# latch_sdc_sch.net
KiCad netlist of a schematic drawn in Altium Designer
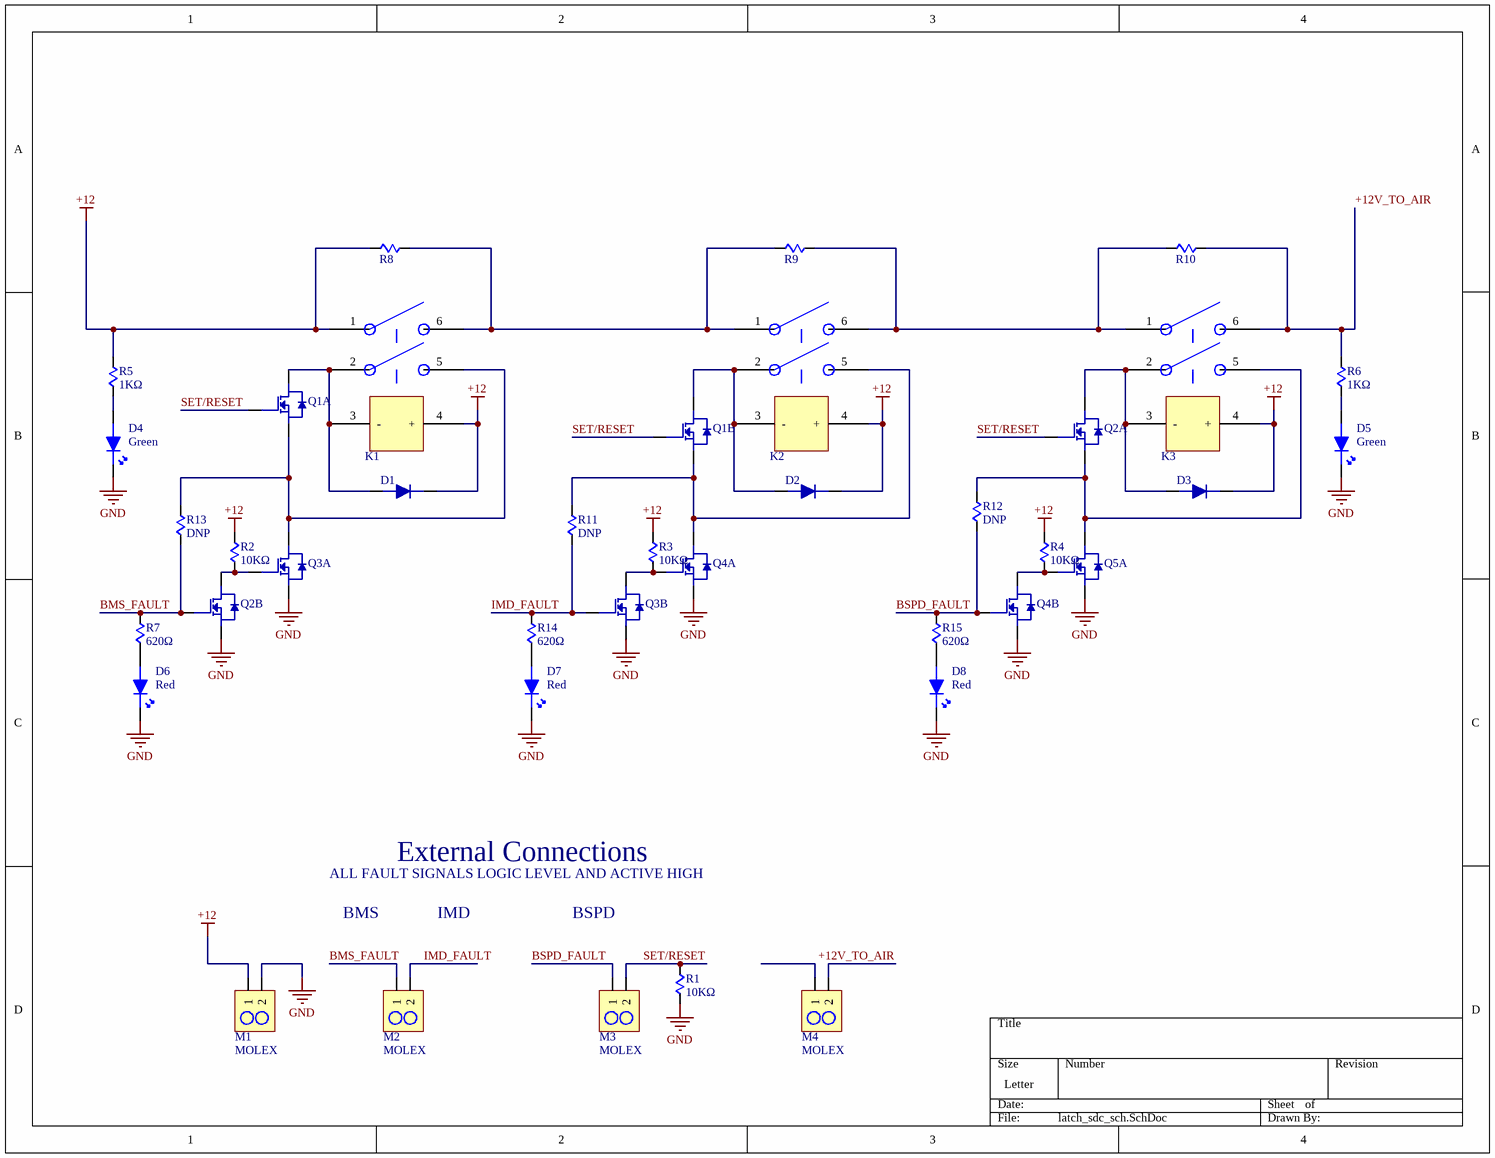
[diagram p0: latch_sdc_sch.SchDoc]

(export (version "E")
  (design (tool "Eeschema 10.0.6"))
  (components
    (comp (ref "D1")
      (value "SD560BTR")
      (footprint "DIOM4436X26N")
      (description "DIODE GEN PURP 600V 5A SMB")
      (fields (field (name "MANUFACTURER") "SMC"))
      (libsource (lib "latch_sdc_schlib") (part "SD560BTR"))
    )
    (comp (ref "D2")
      (value "SD560BTR")
      (footprint "DIOM4436X26N")
      (description "DIODE GEN PURP 600V 5A SMB")
      (fields (field (name "MANUFACTURER") "SMC"))
      (libsource (lib "latch_sdc_schlib") (part "SD560BTR"))
    )
    (comp (ref "D3")
      (value "SD560BTR")
      (footprint "DIOM4436X26N")
      (description "DIODE GEN PURP 600V 5A SMB")
      (fields (field (name "MANUFACTURER") "SMC"))
      (libsource (lib "latch_sdc_schlib") (part "SD560BTR"))
    )
    (comp (ref "D4")
      (value "Green")
      (footprint "LED GREEN")
      (description "WURTH ELEKTRONIK - 150060VS75000 - LED, 0603, B GREEN,  40MCD, 570NM")
      (libsource (lib "latch_sdc_schlib") (part "150060VS75000"))
    )
    (comp (ref "D5")
      (value "Green")
      (footprint "LED GREEN")
      (description "WURTH ELEKTRONIK - 150060VS75000 - LED, 0603, B GREEN,  40MCD, 570NM")
      (libsource (lib "latch_sdc_schlib") (part "150060VS75000"))
    )
    (comp (ref "D6")
      (value "Red")
      (footprint "LED RED")
      (description "WURTH ELEKTRONIK - 150060RS75000 - LED, 0603, RED, 250MCD, 625NM")
      (libsource (lib "latch_sdc_schlib") (part "150060RS75000"))
    )
    (comp (ref "D7")
      (value "Red")
      (footprint "LED RED")
      (description "WURTH ELEKTRONIK - 150060RS75000 - LED, 0603, RED, 250MCD, 625NM")
      (libsource (lib "latch_sdc_schlib") (part "150060RS75000"))
    )
    (comp (ref "D8")
      (value "Red")
      (footprint "LED RED")
      (description "WURTH ELEKTRONIK - 150060RS75000 - LED, 0603, RED, 250MCD, 625NM")
      (libsource (lib "latch_sdc_schlib") (part "150060RS75000"))
    )
    (comp (ref "K1")
      (value "3A")
      (footprint "RELAY02_FOOTPRINT")
      (fields
        (field (name "MANUFACTURER") "TE Connectivity")
        (field (name "MANUFACTURER PART NUMBER") "OSA-SS-212DM3,000")
      )
      (libsource (lib "latch_sdc_schlib") (part "OSA-SS-212DM3,000"))
    )
    (comp (ref "K2")
      (value "3A")
      (footprint "RELAY02_FOOTPRINT")
      (fields
        (field (name "MANUFACTURER") "TE Connectivity")
        (field (name "MANUFACTURER PART NUMBER") "OSA-SS-212DM3,000")
      )
      (libsource (lib "latch_sdc_schlib") (part "OSA-SS-212DM3,000"))
    )
    (comp (ref "K3")
      (value "3A")
      (footprint "RELAY02_FOOTPRINT")
      (fields
        (field (name "MANUFACTURER") "TE Connectivity")
        (field (name "MANUFACTURER PART NUMBER") "OSA-SS-212DM3,000")
      )
      (libsource (lib "latch_sdc_schlib") (part "OSA-SS-212DM3,000"))
    )
    (comp (ref "M1")
      (value "MOLEX")
      (footprint "MOLEX 1")
      (description "MOLEX - 43650-0200 - CONNECTOR, HEADER, 2POS, 1ROW, 3MM")
      (fields (field (name "MANUFACTURER") "Molex") (field (name "MANUFACTURER PART NUMBER") "43650-0200"))
      (libsource (lib "latch_sdc_schlib") (part "43650-0200"))
    )
    (comp (ref "M2")
      (value "MOLEX")
      (footprint "MOLEX 1")
      (description "MOLEX - 43650-0200 - CONNECTOR, HEADER, 2POS, 1ROW, 3MM")
      (fields (field (name "MANUFACTURER") "Molex") (field (name "MANUFACTURER PART NUMBER") "43650-0200"))
      (libsource (lib "latch_sdc_schlib") (part "43650-0200"))
    )
    (comp (ref "M3")
      (value "MOLEX")
      (footprint "MOLEX 1")
      (description "MOLEX - 43650-0200 - CONNECTOR, HEADER, 2POS, 1ROW, 3MM")
      (fields (field (name "MANUFACTURER") "Molex") (field (name "MANUFACTURER PART NUMBER") "43650-0200"))
      (libsource (lib "latch_sdc_schlib") (part "43650-0200"))
    )
    (comp (ref "M4")
      (value "MOLEX")
      (footprint "MOLEX 1")
      (description "MOLEX - 43650-0200 - CONNECTOR, HEADER, 2POS, 1ROW, 3MM")
      (fields (field (name "MANUFACTURER") "Molex") (field (name "MANUFACTURER PART NUMBER") "43650-0200"))
      (libsource (lib "latch_sdc_schlib") (part "43650-0200"))
    )
    (comp (ref "Q1")
      (value "DMN2029USD-13")
      (footprint "SOIC127P600X175-8N")
      (description "MOSFET 2N-CH 20V 5.8A 8SO")
      (fields (field (name "MANUFACTURER") "Diodes"))
      (libsource (lib "latch_sdc_schlib") (part "DMN2029USD-13"))
    )
    (comp (ref "Q2")
      (value "DMN2029USD-13")
      (footprint "SOIC127P600X175-8N")
      (description "MOSFET 2N-CH 20V 5.8A 8SO")
      (fields (field (name "MANUFACTURER") "Diodes"))
      (libsource (lib "latch_sdc_schlib") (part "DMN2029USD-13"))
    )
    (comp (ref "Q3")
      (value "DMN2029USD-13")
      (footprint "SOIC127P600X175-8N")
      (description "MOSFET 2N-CH 20V 5.8A 8SO")
      (fields (field (name "MANUFACTURER") "Diodes"))
      (libsource (lib "latch_sdc_schlib") (part "DMN2029USD-13"))
    )
    (comp (ref "Q4")
      (value "DMN2029USD-13")
      (footprint "SOIC127P600X175-8N")
      (description "MOSFET 2N-CH 20V 5.8A 8SO")
      (fields (field (name "MANUFACTURER") "Diodes"))
      (libsource (lib "latch_sdc_schlib") (part "DMN2029USD-13"))
    )
    (comp (ref "Q5")
      (value "DMN2029USD-13")
      (footprint "SOIC127P600X175-8N")
      (description "MOSFET 2N-CH 20V 5.8A 8SO")
      (fields (field (name "MANUFACTURER") "Diodes"))
      (libsource (lib "latch_sdc_schlib") (part "DMN2029USD-13"))
    )
    (comp (ref "R1")
      (value "10KΩ")
      (footprint "10KOHM")
      (description "RES 10K OHM 1% 1/8W 0603")
      (fields
        (field (name "MANUFACTURER") "Stackpole Electronics")
        (field (name "MANUFACTURER PART NUMBER") "RNCP0603FTD10K0")
      )
      (libsource (lib "latch_sdc_schlib") (part "RNCP0603FTD10K0"))
    )
    (comp (ref "R2")
      (value "10KΩ")
      (footprint "10KOHM")
      (description "RES 10K OHM 1% 1/8W 0603")
      (fields
        (field (name "MANUFACTURER") "Stackpole Electronics")
        (field (name "MANUFACTURER PART NUMBER") "RNCP0603FTD10K0")
      )
      (libsource (lib "latch_sdc_schlib") (part "RNCP0603FTD10K0"))
    )
    (comp (ref "R3")
      (value "10KΩ")
      (footprint "10KOHM")
      (description "RES 10K OHM 1% 1/8W 0603")
      (fields
        (field (name "MANUFACTURER") "Stackpole Electronics")
        (field (name "MANUFACTURER PART NUMBER") "RNCP0603FTD10K0")
      )
      (libsource (lib "latch_sdc_schlib") (part "RNCP0603FTD10K0"))
    )
    (comp (ref "R4")
      (value "10KΩ")
      (footprint "10KOHM")
      (description "RES 10K OHM 1% 1/8W 0603")
      (fields
        (field (name "MANUFACTURER") "Stackpole Electronics")
        (field (name "MANUFACTURER PART NUMBER") "RNCP0603FTD10K0")
      )
      (libsource (lib "latch_sdc_schlib") (part "RNCP0603FTD10K0"))
    )
    (comp (ref "R5")
      (value "1KΩ")
      (footprint "1KOHM")
      (description "YAGEO - RC0201FR-071KL - DICKSCHICHTWIDERSTAND 1K 1% 0.05W 0201")
      (fields (field (name "TOLERANCE") "1%"))
      (libsource (lib "latch_sdc_schlib") (part "RC0201FR-071KL"))
    )
    (comp (ref "R6")
      (value "1KΩ")
      (footprint "1KOHM")
      (description "YAGEO - RC0201FR-071KL - DICKSCHICHTWIDERSTAND 1K 1% 0.05W 0201")
      (fields (field (name "TOLERANCE") "1%"))
      (libsource (lib "latch_sdc_schlib") (part "RC0201FR-071KL"))
    )
    (comp (ref "R7")
      (value "620Ω")
      (footprint "620OHM")
      (description "RC0201 Series 0201 0.05 W 620 Ohms 1% ±200 ppm/°C SMT Thick Film Chip Resistor")
      (fields (field (name "TOLERANCE") "1%"))
      (libsource (lib "latch_sdc_schlib") (part "RC0201FR-07620RL"))
    )
    (comp (ref "R8")
      (value "RMCF0603ZT0R00")
      (footprint "0OHM")
      (description "RES 0 OHM JUMPER 1/10W 0603")
      (fields (field (name "MANUFACTURER") "Stackpole Electronics"))
      (libsource (lib "latch_sdc_schlib") (part "RMCF0603ZT0R00"))
    )
    (comp (ref "R9")
      (value "RMCF0603ZT0R00")
      (footprint "0OHM")
      (description "RES 0 OHM JUMPER 1/10W 0603")
      (fields (field (name "MANUFACTURER") "Stackpole Electronics"))
      (libsource (lib "latch_sdc_schlib") (part "RMCF0603ZT0R00"))
    )
    (comp (ref "R10")
      (value "RMCF0603ZT0R00")
      (footprint "0OHM")
      (description "RES 0 OHM JUMPER 1/10W 0603")
      (fields (field (name "MANUFACTURER") "Stackpole Electronics"))
      (libsource (lib "latch_sdc_schlib") (part "RMCF0603ZT0R00"))
    )
    (comp (ref "R11")
      (value "DNP")
      (footprint "0OHM")
      (description "RES 0 OHM JUMPER 1/10W 0603")
      (fields
        (field (name "MANUFACTURER") "Stackpole Electronics")
        (field (name "MANUFACTURER PART NUMBER") "RMCF0603ZT0R00")
      )
      (libsource (lib "latch_sdc_schlib") (part "RMCF0603ZT0R00_1"))
    )
    (comp (ref "R12")
      (value "DNP")
      (footprint "0OHM")
      (description "RES 0 OHM JUMPER 1/10W 0603")
      (fields
        (field (name "MANUFACTURER") "Stackpole Electronics")
        (field (name "MANUFACTURER PART NUMBER") "RMCF0603ZT0R00")
      )
      (libsource (lib "latch_sdc_schlib") (part "RMCF0603ZT0R00_1"))
    )
    (comp (ref "R13")
      (value "DNP")
      (footprint "0OHM")
      (description "RES 0 OHM JUMPER 1/10W 0603")
      (fields
        (field (name "MANUFACTURER") "Stackpole Electronics")
        (field (name "MANUFACTURER PART NUMBER") "RMCF0603ZT0R00")
      )
      (libsource (lib "latch_sdc_schlib") (part "RMCF0603ZT0R00_1"))
    )
    (comp (ref "R14")
      (value "620Ω")
      (footprint "620OHM")
      (description "RC0201 Series 0201 0.05 W 620 Ohms 1% ±200 ppm/°C SMT Thick Film Chip Resistor")
      (fields (field (name "TOLERANCE") "1%"))
      (libsource (lib "latch_sdc_schlib") (part "RC0201FR-07620RL"))
    )
    (comp (ref "R15")
      (value "620Ω")
      (footprint "620OHM")
      (description "RC0201 Series 0201 0.05 W 620 Ohms 1% ±200 ppm/°C SMT Thick Film Chip Resistor")
      (fields (field (name "TOLERANCE") "1%"))
      (libsource (lib "latch_sdc_schlib") (part "RC0201FR-07620RL"))
    )
  )
  (nets
    (net (code "1") (name "+12") (class "Default")
      (node (ref "D1") (pin "2") (pinfunction "2_2") (pintype "passive"))
      (node (ref "D2") (pin "2") (pinfunction "2_2") (pintype "passive"))
      (node (ref "D3") (pin "2") (pinfunction "2_2") (pintype "passive"))
      (node (ref "K1") (pin "1") (pintype "passive"))
      (node (ref "K1") (pin "4") (pinfunction "+_4") (pintype "passive"))
      (node (ref "K2") (pin "4") (pinfunction "+_4") (pintype "passive"))
      (node (ref "K3") (pin "4") (pinfunction "+_4") (pintype "passive"))
      (node (ref "M1") (pin "1") (pinfunction "1_1") (pintype "passive"))
      (node (ref "R2") (pin "1") (pinfunction "1_1") (pintype "passive"))
      (node (ref "R3") (pin "1") (pinfunction "1_1") (pintype "passive"))
      (node (ref "R4") (pin "1") (pinfunction "1_1") (pintype "passive"))
      (node (ref "R5") (pin "2") (pinfunction "2_2") (pintype "passive"))
      (node (ref "R8") (pin "1") (pinfunction "1_1") (pintype "passive"))
    )
    (net (code "2") (name "/+12V_TO_AIR") (class "Default")
      (node (ref "K3") (pin "6") (pintype "passive"))
      (node (ref "M4") (pin "2") (pinfunction "2_2") (pintype "passive"))
      (node (ref "R10") (pin "2") (pinfunction "2_2") (pintype "passive"))
      (node (ref "R6") (pin "2") (pinfunction "2_2") (pintype "passive"))
    )
    (net (code "3") (name "/BMS_FAULT") (class "Default")
      (node (ref "M2") (pin "1") (pinfunction "1_1") (pintype "passive"))
      (node (ref "Q2") (pin "4") (pinfunction "G2_4") (pintype "passive"))
      (node (ref "R13") (pin "1") (pinfunction "1_1") (pintype "passive"))
      (node (ref "R7") (pin "2") (pinfunction "2_2") (pintype "passive"))
    )
    (net (code "4") (name "/BSPD_FAULT") (class "Default")
      (node (ref "M3") (pin "1") (pinfunction "1_1") (pintype "passive"))
      (node (ref "Q4") (pin "4") (pinfunction "G2_4") (pintype "passive"))
      (node (ref "R12") (pin "1") (pinfunction "1_1") (pintype "passive"))
      (node (ref "R15") (pin "2") (pinfunction "2_2") (pintype "passive"))
    )
    (net (code "5") (name "/IMD_FAULT") (class "Default")
      (node (ref "M2") (pin "2") (pinfunction "2_2") (pintype "passive"))
      (node (ref "Q3") (pin "4") (pinfunction "G2_4") (pintype "passive"))
      (node (ref "R11") (pin "1") (pinfunction "1_1") (pintype "passive"))
      (node (ref "R14") (pin "2") (pinfunction "2_2") (pintype "passive"))
    )
    (net (code "6") (name "/SET{slash}RESET") (class "Default")
      (node (ref "M3") (pin "2") (pinfunction "2_2") (pintype "passive"))
      (node (ref "Q1") (pin "2") (pinfunction "G1_2") (pintype "passive"))
      (node (ref "Q1") (pin "4") (pinfunction "G2_4") (pintype "passive"))
      (node (ref "Q2") (pin "2") (pinfunction "G1_2") (pintype "passive"))
      (node (ref "R1") (pin "1") (pinfunction "1_1") (pintype "passive"))
    )
    (net (code "7") (name "GND") (class "Default")
      (node (ref "D4") (pin "2") (pinfunction "2_2") (pintype "passive"))
      (node (ref "D5") (pin "2") (pinfunction "2_2") (pintype "passive"))
      (node (ref "D6") (pin "2") (pinfunction "2_2") (pintype "passive"))
      (node (ref "D7") (pin "2") (pinfunction "2_2") (pintype "passive"))
      (node (ref "D8") (pin "2") (pinfunction "2_2") (pintype "passive"))
      (node (ref "M1") (pin "2") (pinfunction "2_2") (pintype "passive"))
      (node (ref "Q2") (pin "3") (pinfunction "S2_3") (pintype "passive"))
      (node (ref "Q3") (pin "1") (pinfunction "S1_1") (pintype "passive"))
      (node (ref "Q3") (pin "3") (pinfunction "S2_3") (pintype "passive"))
      (node (ref "Q4") (pin "1") (pinfunction "S1_1") (pintype "passive"))
      (node (ref "Q4") (pin "3") (pinfunction "S2_3") (pintype "passive"))
      (node (ref "Q5") (pin "1") (pinfunction "S1_1") (pintype "passive"))
      (node (ref "R1") (pin "2") (pinfunction "2_2") (pintype "passive"))
    )
    (net (code "8") (name "Net-(D4-Pad1)") (class "Default")
      (node (ref "D4") (pin "1") (pinfunction "1_1") (pintype "passive"))
      (node (ref "R5") (pin "1") (pinfunction "1_1") (pintype "passive"))
    )
    (net (code "9") (name "Net-(D5-Pad1)") (class "Default")
      (node (ref "D5") (pin "1") (pinfunction "1_1") (pintype "passive"))
      (node (ref "R6") (pin "1") (pinfunction "1_1") (pintype "passive"))
    )
    (net (code "10") (name "Net-(D6-Pad1)") (class "Default")
      (node (ref "D6") (pin "1") (pinfunction "1_1") (pintype "passive"))
      (node (ref "R7") (pin "1") (pinfunction "1_1") (pintype "passive"))
    )
    (net (code "11") (name "Net-(D7-Pad1)") (class "Default")
      (node (ref "D7") (pin "1") (pinfunction "1_1") (pintype "passive"))
      (node (ref "R14") (pin "1") (pinfunction "1_1") (pintype "passive"))
    )
    (net (code "12") (name "Net-(D8-Pad1)") (class "Default")
      (node (ref "D8") (pin "1") (pinfunction "1_1") (pintype "passive"))
      (node (ref "R15") (pin "1") (pinfunction "1_1") (pintype "passive"))
    )
    (net (code "13") (name "Net-(K1--)") (class "Default")
      (node (ref "D1") (pin "1") (pinfunction "1_1") (pintype "passive"))
      (node (ref "K1") (pin "2") (pintype "passive"))
      (node (ref "K1") (pin "3") (pinfunction "-_3") (pintype "passive"))
      (node (ref "Q1") (pin "8") (pinfunction "D1_8") (pintype "passive"))
    )
    (net (code "14") (name "Net-(K1-Pad6)") (class "Default")
      (node (ref "K1") (pin "6") (pintype "passive"))
      (node (ref "K2") (pin "1") (pintype "passive"))
      (node (ref "R8") (pin "2") (pinfunction "2_2") (pintype "passive"))
      (node (ref "R9") (pin "1") (pinfunction "1_1") (pintype "passive"))
    )
    (net (code "15") (name "Net-(K2--)") (class "Default")
      (node (ref "D2") (pin "1") (pinfunction "1_1") (pintype "passive"))
      (node (ref "K2") (pin "2") (pintype "passive"))
      (node (ref "K2") (pin "3") (pinfunction "-_3") (pintype "passive"))
      (node (ref "Q1") (pin "5") (pinfunction "D2_5") (pintype "passive"))
    )
    (net (code "16") (name "Net-(K2-Pad6)") (class "Default")
      (node (ref "K2") (pin "6") (pintype "passive"))
      (node (ref "K3") (pin "1") (pintype "passive"))
      (node (ref "R10") (pin "1") (pinfunction "1_1") (pintype "passive"))
      (node (ref "R9") (pin "2") (pinfunction "2_2") (pintype "passive"))
    )
    (net (code "17") (name "Net-(K3--)") (class "Default")
      (node (ref "D3") (pin "1") (pinfunction "1_1") (pintype "passive"))
      (node (ref "K3") (pin "2") (pintype "passive"))
      (node (ref "K3") (pin "3") (pinfunction "-_3") (pintype "passive"))
      (node (ref "Q2") (pin "8") (pinfunction "D1_8") (pintype "passive"))
    )
    (net (code "18") (name "Net-(Q1A-S1)") (class "Default")
      (node (ref "K1") (pin "5") (pintype "passive"))
      (node (ref "Q1") (pin "1") (pinfunction "S1_1") (pintype "passive"))
      (node (ref "Q3") (pin "8") (pinfunction "D1_8") (pintype "passive"))
      (node (ref "R13") (pin "2") (pinfunction "2_2") (pintype "passive"))
    )
    (net (code "19") (name "Net-(Q1B-S2)") (class "Default")
      (node (ref "K2") (pin "5") (pintype "passive"))
      (node (ref "Q1") (pin "3") (pinfunction "S2_3") (pintype "passive"))
      (node (ref "Q4") (pin "8") (pinfunction "D1_8") (pintype "passive"))
      (node (ref "R11") (pin "2") (pinfunction "2_2") (pintype "passive"))
    )
    (net (code "20") (name "Net-(Q2A-S1)") (class "Default")
      (node (ref "K3") (pin "5") (pintype "passive"))
      (node (ref "Q2") (pin "1") (pinfunction "S1_1") (pintype "passive"))
      (node (ref "Q5") (pin "8") (pinfunction "D1_8") (pintype "passive"))
      (node (ref "R12") (pin "2") (pinfunction "2_2") (pintype "passive"))
    )
    (net (code "21") (name "Net-(Q2B-D2)") (class "Default")
      (node (ref "Q2") (pin "5") (pinfunction "D2_5") (pintype "passive"))
      (node (ref "Q3") (pin "2") (pinfunction "G1_2") (pintype "passive"))
      (node (ref "R2") (pin "2") (pinfunction "2_2") (pintype "passive"))
    )
    (net (code "22") (name "Net-(Q3B-D2)") (class "Default")
      (node (ref "Q3") (pin "5") (pinfunction "D2_5") (pintype "passive"))
      (node (ref "Q4") (pin "2") (pinfunction "G1_2") (pintype "passive"))
      (node (ref "R3") (pin "2") (pinfunction "2_2") (pintype "passive"))
    )
    (net (code "23") (name "Net-(Q4B-D2)") (class "Default")
      (node (ref "Q4") (pin "5") (pinfunction "D2_5") (pintype "passive"))
      (node (ref "Q5") (pin "2") (pinfunction "G1_2") (pintype "passive"))
      (node (ref "R4") (pin "2") (pinfunction "2_2") (pintype "passive"))
    )
    (net (code "24") (name "unconnected-(M4-Pad1)") (class "Default")
      (node (ref "M4") (pin "1") (pinfunction "1_1") (pintype "passive"))
    )
  )
)
